# PVLoad.net
KiCad netlist of a schematic drawn in Altium Designer
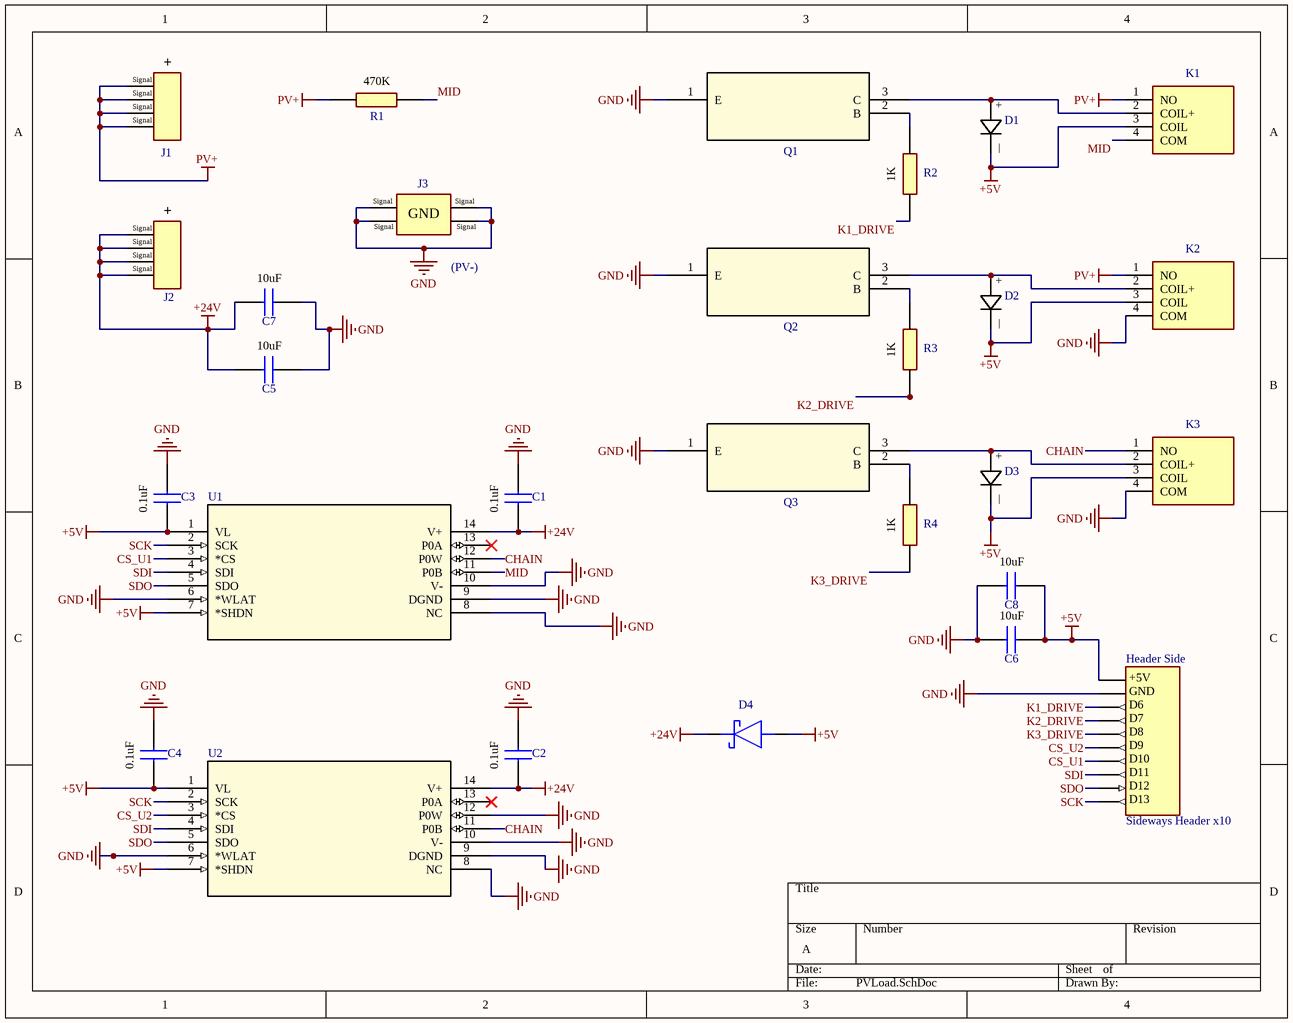
[diagram p0: PVLoad.SchDoc]

(export (version "E")
  (design (tool "Eeschema 10.0.6"))
  (components
    (comp (ref "C1")
      (value "0.1uF Capacitor")
      (footprint "CAPC2012X95N 0.1uF")
      (description "Capacitor")
      (fields
        (field (name "MANUFACTURER_PART_NUMBER") "CL21B104KBCNNNC")
        (field (name "MOUSER PART NUMBER") "187-CL21B104KBCNNNC")
      )
      (libsource (lib "PVLoad_Schlib") (part "0.1uF Capacitor"))
    )
    (comp (ref "C2")
      (value "0.1uF Capacitor")
      (footprint "CAPC2012X95N 0.1uF")
      (description "Capacitor")
      (fields
        (field (name "MANUFACTURER_PART_NUMBER") "CL21B104KBCNNNC")
        (field (name "MOUSER PART NUMBER") "187-CL21B104KBCNNNC")
      )
      (libsource (lib "PVLoad_Schlib") (part "0.1uF Capacitor"))
    )
    (comp (ref "C3")
      (value "0.1uF Capacitor")
      (footprint "CAPC2012X95N 0.1uF")
      (description "Capacitor")
      (fields
        (field (name "MANUFACTURER_PART_NUMBER") "CL21B104KBCNNNC")
        (field (name "MOUSER PART NUMBER") "187-CL21B104KBCNNNC")
      )
      (libsource (lib "PVLoad_Schlib") (part "0.1uF Capacitor"))
    )
    (comp (ref "C4")
      (value "0.1uF Capacitor")
      (footprint "CAPC2012X95N 0.1uF")
      (description "Capacitor")
      (fields
        (field (name "MANUFACTURER_PART_NUMBER") "CL21B104KBCNNNC")
        (field (name "MOUSER PART NUMBER") "187-CL21B104KBCNNNC")
      )
      (libsource (lib "PVLoad_Schlib") (part "0.1uF Capacitor"))
    )
    (comp (ref "C5")
      (value "10uF Capacitor")
      (footprint "CAPC3225X270N 10uF")
      (description "Capacitor")
      (fields
        (field (name "MANUFACTURER_PART_NUMBER") "CL32B106KBJNNNE")
        (field (name "MOUSER PART NUMBER") "187-CL32B106KBJNNNE")
      )
      (libsource (lib "PVLoad_Schlib") (part "10uF Capacitor"))
    )
    (comp (ref "C6")
      (value "10uF Capacitor")
      (footprint "CAPC3225X270N 10uF")
      (description "Capacitor")
      (fields
        (field (name "MANUFACTURER_PART_NUMBER") "CL32B106KBJNNNE")
        (field (name "MOUSER PART NUMBER") "187-CL32B106KBJNNNE")
      )
      (libsource (lib "PVLoad_Schlib") (part "10uF Capacitor"))
    )
    (comp (ref "C7")
      (value "10uF Capacitor")
      (footprint "CAPC3225X270N 10uF")
      (description "Capacitor")
      (fields
        (field (name "MANUFACTURER_PART_NUMBER") "CL32B106KBJNNNE")
        (field (name "MOUSER PART NUMBER") "187-CL32B106KBJNNNE")
      )
      (libsource (lib "PVLoad_Schlib") (part "10uF Capacitor"))
    )
    (comp (ref "C8")
      (value "10uF Capacitor")
      (footprint "CAPC3225X270N 10uF")
      (description "Capacitor")
      (fields
        (field (name "MANUFACTURER_PART_NUMBER") "CL32B106KBJNNNE")
        (field (name "MOUSER PART NUMBER") "187-CL32B106KBJNNNE")
      )
      (libsource (lib "PVLoad_Schlib") (part "10uF Capacitor"))
    )
    (comp (ref "D1")
      (value "1N4148")
      (footprint "AXIAL_017AG_T26_ONS")
      (description "No Description Available")
      (fields (field (name "COPYRIGHT") "Copyright (C) 2026 Ultra Librarian. All rights reserved."))
      (libsource (lib "PVLoad_Schlib") (part "1N4148"))
    )
    (comp (ref "D2")
      (value "1N4148")
      (footprint "AXIAL_017AG_T26_ONS")
      (description "No Description Available")
      (fields (field (name "COPYRIGHT") "Copyright (C) 2026 Ultra Librarian. All rights reserved."))
      (libsource (lib "PVLoad_Schlib") (part "1N4148"))
    )
    (comp (ref "D3")
      (value "1N4148")
      (footprint "AXIAL_017AG_T26_ONS")
      (description "No Description Available")
      (fields (field (name "COPYRIGHT") "Copyright (C) 2026 Ultra Librarian. All rights reserved."))
      (libsource (lib "PVLoad_Schlib") (part "1N4148"))
    )
    (comp (ref "D4")
      (value "1N5819HW1-7-F")
      (footprint "SODFL3518X115N")
      (description "1N5819 Schottky Diode 40V 1A SOD123F")
      (fields (field (name "MOUSER PART NUMBER") "621-1N5819HW1-7-F"))
      (libsource (lib "PVLoad_Schlib") (part "1N5819HW1-7-F"))
    )
    (comp (ref "Header Side")
      (value "Sideways Header x10")
      (footprint "Sideways Header x10")
      (libsource (lib "PVLoad_Schlib") (part "Sideways Header x10"))
    )
    (comp (ref "J1")
      (value "CT3151-2")
      (footprint "CALTEST_CT3151-2")
      (description "Banana Jack Connector Standard Banana Solder Red")
      (fields (field (name "MF") "Cal Test"))
      (libsource (lib "PVLoad_Schlib") (part "CT3151-2"))
    )
    (comp (ref "J2")
      (value "CT3151-2")
      (footprint "CALTEST_CT3151-2")
      (description "Banana Jack Connector Standard Banana Solder Red")
      (fields (field (name "MF") "Cal Test"))
      (libsource (lib "PVLoad_Schlib") (part "CT3151-2"))
    )
    (comp (ref "J3")
      (value "CT3151-0")
      (footprint "CT31510")
      (description "4mm Safety Jack Horizontal PCB Mount")
      (fields (field (name "MOUSER PART NUMBER") "510-CT3151-0"))
      (libsource (lib "PVLoad_Schlib") (part "CT3151-0"))
    )
    (comp (ref "K1")
      (value "HE3621A0540")
      (footprint "HE3621A0540")
      (description "Reed Relay 5VDC 500Ohm 0.5A SPST-NO(20.2x6.05x7.87)mm THT Dry")
      (fields (field (name "MOUSER PART NUMBER") "934-HE3621A0540"))
      (libsource (lib "PVLoad_Schlib") (part "HE3621A0540"))
    )
    (comp (ref "K2")
      (value "HE3621A0540")
      (footprint "HE3621A0540")
      (description "Reed Relay 5VDC 500Ohm 0.5A SPST-NO(20.2x6.05x7.87)mm THT Dry")
      (fields (field (name "MOUSER PART NUMBER") "934-HE3621A0540"))
      (libsource (lib "PVLoad_Schlib") (part "HE3621A0540"))
    )
    (comp (ref "K3")
      (value "HE3621A0540")
      (footprint "HE3621A0540")
      (description "Reed Relay 5VDC 500Ohm 0.5A SPST-NO(20.2x6.05x7.87)mm THT Dry")
      (fields (field (name "MOUSER PART NUMBER") "934-HE3621A0540"))
      (libsource (lib "PVLoad_Schlib") (part "HE3621A0540"))
    )
    (comp (ref "Q1")
      (value "2N3904BU")
      (footprint "TO-92_FAS")
      (description "No Description Available")
      (fields (field (name "COPYRIGHT") "Copyright (C) 2026 Ultra Librarian. All rights reserved."))
      (libsource (lib "PVLoad_Schlib") (part "2N3904BU"))
    )
    (comp (ref "Q2")
      (value "2N3904BU")
      (footprint "TO-92_FAS")
      (description "No Description Available")
      (fields (field (name "COPYRIGHT") "Copyright (C) 2026 Ultra Librarian. All rights reserved."))
      (libsource (lib "PVLoad_Schlib") (part "2N3904BU"))
    )
    (comp (ref "Q3")
      (value "2N3904BU")
      (footprint "TO-92_FAS")
      (description "No Description Available")
      (fields (field (name "COPYRIGHT") "Copyright (C) 2026 Ultra Librarian. All rights reserved."))
      (libsource (lib "PVLoad_Schlib") (part "2N3904BU"))
    )
    (comp (ref "R1")
      (value "RC0805FR-07470KL")
      (footprint "RESC2012X60N 470K")
      (description "Resistor")
      (fields (field (name "MOUSER PART NUMBER") "603-RC0805FR-07470KL"))
      (libsource (lib "PVLoad_Schlib") (part "RC0805FR-07470KL"))
    )
    (comp (ref "R2")
      (value "RC0805FR-071KL")
      (footprint "RESC2012X60N 1K")
      (description "Resistor")
      (libsource (lib "PVLoad_Schlib") (part "RC0805FR-071KL"))
    )
    (comp (ref "R3")
      (value "RC0805FR-071KL")
      (footprint "RESC2012X60N 1K")
      (description "Resistor")
      (libsource (lib "PVLoad_Schlib") (part "RC0805FR-071KL"))
    )
    (comp (ref "R4")
      (value "RC0805FR-071KL")
      (footprint "RESC2012X60N 1K")
      (description "Resistor")
      (libsource (lib "PVLoad_Schlib") (part "RC0805FR-071KL"))
    )
    (comp (ref "U1")
      (value "MCP41HV51-502E/ST")
      (footprint "TSSOP14_MC_MCH-M")
      (description "No Description Available")
      (fields (field (name "COPYRIGHT") "Copyright (C) 2026 Ultra Librarian. All rights reserved."))
      (libsource (lib "PVLoad_Schlib") (part "MCP41HV51-502EST"))
    )
    (comp (ref "U2")
      (value "MCP41HV51-502E/ST")
      (footprint "TSSOP14_MC_MCH-M")
      (description "No Description Available")
      (fields (field (name "COPYRIGHT") "Copyright (C) 2026 Ultra Librarian. All rights reserved."))
      (libsource (lib "PVLoad_Schlib") (part "MCP41HV51-502EST"))
    )
  )
  (nets
    (net (code "1") (name "+5V") (class "Default")
      (node (ref "C3") (pin "1") (pinfunction "1_1") (pintype "passive"))
      (node (ref "C4") (pin "1") (pinfunction "1_1") (pintype "passive"))
      (node (ref "C6") (pin "2") (pinfunction "2_2") (pintype "passive"))
      (node (ref "C8") (pin "2") (pinfunction "2_2") (pintype "passive"))
      (node (ref "D1") (pin "1") (pinfunction "1_1") (pintype "passive"))
      (node (ref "D2") (pin "1") (pinfunction "1_1") (pintype "passive"))
      (node (ref "D3") (pin "1") (pinfunction "1_1") (pintype "passive"))
      (node (ref "D4") (pin "2") (pinfunction "A_2") (pintype "passive"))
      (node (ref "Header Side") (pin "1") (pinfunction "1_1") (pintype "power_in"))
      (node (ref "K1") (pin "3") (pinfunction "COIL_3") (pintype "passive"))
      (node (ref "K2") (pin "3") (pinfunction "COIL_3") (pintype "passive"))
      (node (ref "K3") (pin "3") (pinfunction "COIL_3") (pintype "passive"))
      (node (ref "U1") (pin "1") (pinfunction "VL_1") (pintype "power_in"))
      (node (ref "U1") (pin "7") (pinfunction "*SHDN_7") (pintype "input"))
      (node (ref "U2") (pin "1") (pinfunction "VL_1") (pintype "power_in"))
      (node (ref "U2") (pin "7") (pinfunction "*SHDN_7") (pintype "input"))
    )
    (net (code "2") (name "+24V") (class "Default")
      (node (ref "C1") (pin "1") (pinfunction "1_1") (pintype "passive"))
      (node (ref "C2") (pin "1") (pinfunction "1_1") (pintype "passive"))
      (node (ref "C5") (pin "1") (pinfunction "1_1") (pintype "passive"))
      (node (ref "C7") (pin "1") (pinfunction "1_1") (pintype "passive"))
      (node (ref "D4") (pin "1") (pinfunction "K_1") (pintype "passive"))
      (node (ref "J2") (pin "1") (pinfunction "1_1") (pintype "passive"))
      (node (ref "J2") (pin "2") (pinfunction "1_2") (pintype "passive"))
      (node (ref "J2") (pin "3") (pinfunction "1_3") (pintype "passive"))
      (node (ref "J2") (pin "4") (pinfunction "1_4") (pintype "passive"))
      (node (ref "U1") (pin "14") (pinfunction "V+_14") (pintype "power_in"))
      (node (ref "U2") (pin "14") (pinfunction "V+_14") (pintype "power_in"))
    )
    (net (code "3") (name "/CHAIN") (class "Default")
      (node (ref "K3") (pin "1") (pinfunction "NO_1") (pintype "passive"))
      (node (ref "U1") (pin "12") (pinfunction "P0W_12") (pintype "bidirectional"))
      (node (ref "U2") (pin "11") (pinfunction "P0B_11") (pintype "bidirectional"))
    )
    (net (code "4") (name "/CS_U1") (class "Default")
      (node (ref "Header Side") (pin "7") (pinfunction "7_7") (pintype "output"))
      (node (ref "U1") (pin "3") (pinfunction "*CS_3") (pintype "input"))
    )
    (net (code "5") (name "/CS_U2") (class "Default")
      (node (ref "Header Side") (pin "6") (pinfunction "6_6") (pintype "output"))
      (node (ref "U2") (pin "3") (pinfunction "*CS_3") (pintype "input"))
    )
    (net (code "6") (name "/K1_DRIVE") (class "Default")
      (node (ref "Header Side") (pin "3") (pinfunction "3_3") (pintype "output"))
      (node (ref "R2") (pin "1") (pinfunction "1_1") (pintype "passive"))
    )
    (net (code "7") (name "/K2_DRIVE") (class "Default")
      (node (ref "Header Side") (pin "4") (pinfunction "4_4") (pintype "output"))
      (node (ref "R3") (pin "1") (pinfunction "1_1") (pintype "passive"))
    )
    (net (code "8") (name "/K3_DRIVE") (class "Default")
      (node (ref "Header Side") (pin "5") (pinfunction "5_5") (pintype "output"))
      (node (ref "R4") (pin "1") (pinfunction "1_1") (pintype "passive"))
    )
    (net (code "9") (name "/MID") (class "Default")
      (node (ref "K1") (pin "4") (pinfunction "COM_4") (pintype "passive"))
      (node (ref "R1") (pin "2") (pinfunction "2_2") (pintype "passive"))
      (node (ref "U1") (pin "11") (pinfunction "P0B_11") (pintype "bidirectional"))
    )
    (net (code "10") (name "/SCK") (class "Default")
      (node (ref "Header Side") (pin "10") (pinfunction "10_10") (pintype "output"))
      (node (ref "U1") (pin "2") (pinfunction "SCK_2") (pintype "input"))
      (node (ref "U2") (pin "2") (pinfunction "SCK_2") (pintype "input"))
    )
    (net (code "11") (name "/SDI") (class "Default")
      (node (ref "Header Side") (pin "8") (pinfunction "8_8") (pintype "output"))
      (node (ref "U1") (pin "4") (pinfunction "SDI_4") (pintype "input"))
      (node (ref "U2") (pin "4") (pinfunction "SDI_4") (pintype "input"))
    )
    (net (code "12") (name "/SDO") (class "Default")
      (node (ref "Header Side") (pin "9") (pinfunction "9_9") (pintype "input"))
      (node (ref "U1") (pin "5") (pinfunction "SDO_5") (pintype "tri_state"))
      (node (ref "U2") (pin "5") (pinfunction "SDO_5") (pintype "tri_state"))
    )
    (net (code "13") (name "GND") (class "Default")
      (node (ref "C1") (pin "2") (pinfunction "2_2") (pintype "passive"))
      (node (ref "C2") (pin "2") (pinfunction "2_2") (pintype "passive"))
      (node (ref "C3") (pin "2") (pinfunction "2_2") (pintype "passive"))
      (node (ref "C4") (pin "2") (pinfunction "2_2") (pintype "passive"))
      (node (ref "C5") (pin "2") (pinfunction "2_2") (pintype "passive"))
      (node (ref "C6") (pin "1") (pinfunction "1_1") (pintype "passive"))
      (node (ref "C7") (pin "2") (pinfunction "2_2") (pintype "passive"))
      (node (ref "C8") (pin "1") (pinfunction "1_1") (pintype "passive"))
      (node (ref "Header Side") (pin "2") (pinfunction "2_2") (pintype "power_in"))
      (node (ref "J3") (pin "1") (pinfunction "1_1") (pintype "passive"))
      (node (ref "J3") (pin "2") (pinfunction "2_2") (pintype "passive"))
      (node (ref "J3") (pin "3") (pinfunction "3_3") (pintype "passive"))
      (node (ref "J3") (pin "4") (pinfunction "4_4") (pintype "passive"))
      (node (ref "K2") (pin "4") (pinfunction "COM_4") (pintype "passive"))
      (node (ref "K3") (pin "4") (pinfunction "COM_4") (pintype "passive"))
      (node (ref "Q1") (pin "1") (pinfunction "E_1") (pintype "passive"))
      (node (ref "Q2") (pin "1") (pinfunction "E_1") (pintype "passive"))
      (node (ref "Q3") (pin "1") (pinfunction "E_1") (pintype "passive"))
      (node (ref "U1") (pin "10") (pinfunction "V-_10") (pintype "power_in"))
      (node (ref "U1") (pin "6") (pinfunction "*WLAT_6") (pintype "input"))
      (node (ref "U1") (pin "8") (pinfunction "NC_8") (pintype "passive"))
      (node (ref "U1") (pin "9") (pinfunction "DGND_9") (pintype "power_in"))
      (node (ref "U2") (pin "10") (pinfunction "V-_10") (pintype "power_in"))
      (node (ref "U2") (pin "12") (pinfunction "P0W_12") (pintype "bidirectional"))
      (node (ref "U2") (pin "6") (pinfunction "*WLAT_6") (pintype "input"))
      (node (ref "U2") (pin "8") (pinfunction "NC_8") (pintype "passive"))
      (node (ref "U2") (pin "9") (pinfunction "DGND_9") (pintype "power_in"))
    )
    (net (code "14") (name "Net-(K1-COIL+)") (class "Default")
      (node (ref "D1") (pin "2") (pinfunction "2_2") (pintype "passive"))
      (node (ref "K1") (pin "2") (pinfunction "COIL+_2") (pintype "passive"))
      (node (ref "Q1") (pin "3") (pinfunction "C_3") (pintype "passive"))
    )
    (net (code "15") (name "Net-(K2-COIL+)") (class "Default")
      (node (ref "D2") (pin "2") (pinfunction "2_2") (pintype "passive"))
      (node (ref "K2") (pin "2") (pinfunction "COIL+_2") (pintype "passive"))
      (node (ref "Q2") (pin "3") (pinfunction "C_3") (pintype "passive"))
    )
    (net (code "16") (name "Net-(K3-COIL+)") (class "Default")
      (node (ref "D3") (pin "2") (pinfunction "2_2") (pintype "passive"))
      (node (ref "K3") (pin "2") (pinfunction "COIL+_2") (pintype "passive"))
      (node (ref "Q3") (pin "3") (pinfunction "C_3") (pintype "passive"))
    )
    (net (code "17") (name "Net-(Q1-B)") (class "Default")
      (node (ref "Q1") (pin "2") (pinfunction "B_2") (pintype "passive"))
      (node (ref "R2") (pin "2") (pinfunction "2_2") (pintype "passive"))
    )
    (net (code "18") (name "Net-(Q2-B)") (class "Default")
      (node (ref "Q2") (pin "2") (pinfunction "B_2") (pintype "passive"))
      (node (ref "R3") (pin "2") (pinfunction "2_2") (pintype "passive"))
    )
    (net (code "19") (name "Net-(Q3-B)") (class "Default")
      (node (ref "Q3") (pin "2") (pinfunction "B_2") (pintype "passive"))
      (node (ref "R4") (pin "2") (pinfunction "2_2") (pintype "passive"))
    )
    (net (code "20") (name "PV+") (class "Default")
      (node (ref "J1") (pin "1") (pinfunction "1_1") (pintype "passive"))
      (node (ref "J1") (pin "2") (pinfunction "1_2") (pintype "passive"))
      (node (ref "J1") (pin "3") (pinfunction "1_3") (pintype "passive"))
      (node (ref "J1") (pin "4") (pinfunction "1_4") (pintype "passive"))
      (node (ref "K1") (pin "1") (pinfunction "NO_1") (pintype "passive"))
      (node (ref "K2") (pin "1") (pinfunction "NO_1") (pintype "passive"))
      (node (ref "R1") (pin "1") (pinfunction "1_1") (pintype "passive"))
    )
    (net (code "21") (name "unconnected-(U1-P0A-Pad13)") (class "Default")
      (node (ref "U1") (pin "13") (pinfunction "P0A_13") (pintype "bidirectional+no_connect"))
    )
    (net (code "22") (name "unconnected-(U2-P0A-Pad13)") (class "Default")
      (node (ref "U2") (pin "13") (pinfunction "P0A_13") (pintype "bidirectional+no_connect"))
    )
  )
)
